# StepperMotorAuxBoard.net
KiCad netlist of a schematic drawn in Altium Designer
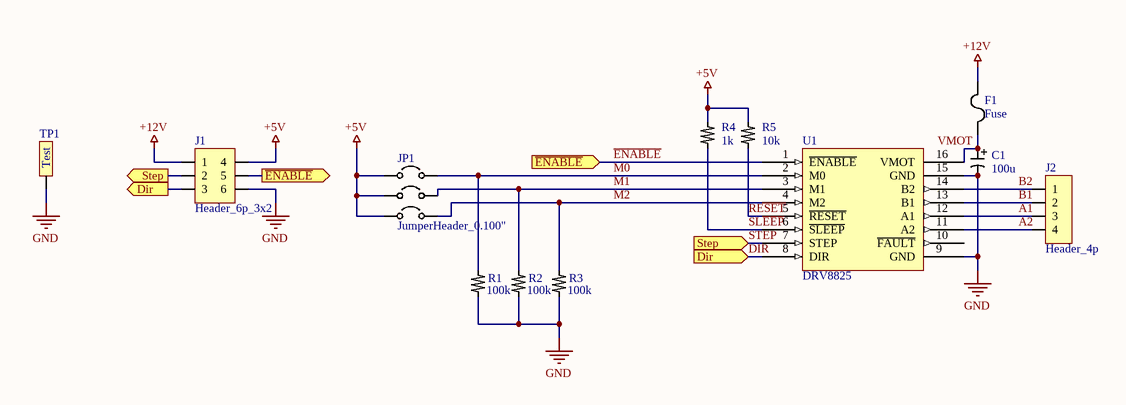
[diagram p0: StepperMotorAuxBoard.SchDoc]

(export (version "E")
  (design (tool "Eeschema 10.0.6"))
  (components
    (comp (ref "C1")
      (value "100u")
      (footprint "Capacitor_UVZ2A101MPD")
      (libsource (lib "Schlib") (part "Capacitor Polarized"))
    )
    (comp (ref "F1") (value "Fuse") (footprint "1812_PTC") (libsource (lib "MikesLib") (part "Fuse")))
    (comp (ref "J1")
      (value "Header_6p_3x2")
      (footprint "MOLEX_MiniFitJr_6p")
      (libsource (lib "MikesLib") (part "Header_6p_3x2"))
    )
    (comp (ref "J2")
      (value "Header_4p")
      (footprint "JST-XH_4p")
      (libsource (lib "Schlib") (part "Header_4p"))
    )
    (comp (ref "JP1")
      (value "JumperHeader_0.100\"")
      (footprint "JumperHeader_0.100\"")
      (libsource (lib "Schlib") (part "JumperHeader_0.100{dblquote}"))
    )
    (comp (ref "R1") (value "100k") (footprint "0805") (libsource (lib "Schlib") (part "Resistor")))
    (comp (ref "R2") (value "100k") (footprint "0805") (libsource (lib "Schlib") (part "Resistor")))
    (comp (ref "R3") (value "100k") (footprint "0805") (libsource (lib "Schlib") (part "Resistor")))
    (comp (ref "R4") (value "1k") (footprint "0805") (libsource (lib "Schlib") (part "Resistor")))
    (comp (ref "R5") (value "10k") (footprint "0805") (libsource (lib "Schlib") (part "Resistor")))
    (comp (ref "TP1")
      (value "TestPoint")
      (footprint "MikesLib:TestPoint")
      (libsource (lib "MikesLib") (part "TestPoint"))
    )
    (comp (ref "U1")
      (value "DRV8825")
      (footprint "DRV8825")
      (description "Stepper motor driver")
      (libsource (lib "Schlib") (part "DRV8825"))
    )
  )
  (nets
    (net (code "1") (name "+5V") (class "Default")
      (node (ref "J1") (pin "4") (pinfunction "4_4") (pintype "passive"))
      (node (ref "JP1") (pin "2") (pinfunction "2_2") (pintype "passive"))
      (node (ref "JP1") (pin "4") (pinfunction "4_4") (pintype "passive"))
      (node (ref "JP1") (pin "6") (pinfunction "6_6") (pintype "passive"))
      (node (ref "R4") (pin "2") (pinfunction "2_2") (pintype "passive"))
      (node (ref "R5") (pin "2") (pinfunction "2_2") (pintype "passive"))
    )
    (net (code "2") (name "+12V") (class "Default")
      (node (ref "F1") (pin "2") (pinfunction "2_2") (pintype "passive"))
      (node (ref "J1") (pin "1") (pinfunction "1_1") (pintype "passive"))
    )
    (net (code "3") (name "/A1") (class "Default")
      (node (ref "J2") (pin "3") (pinfunction "3_3") (pintype "passive"))
      (node (ref "U1") (pin "12") (pinfunction "A1_12") (pintype "output"))
    )
    (net (code "4") (name "/A2") (class "Default")
      (node (ref "J2") (pin "4") (pinfunction "4_4") (pintype "passive"))
      (node (ref "U1") (pin "11") (pinfunction "A2_11") (pintype "output"))
    )
    (net (code "5") (name "/B1") (class "Default")
      (node (ref "J2") (pin "2") (pinfunction "2_2") (pintype "passive"))
      (node (ref "U1") (pin "13") (pinfunction "B1_13") (pintype "output"))
    )
    (net (code "6") (name "/B2") (class "Default")
      (node (ref "J2") (pin "1") (pinfunction "1_1") (pintype "passive"))
      (node (ref "U1") (pin "14") (pinfunction "B2_14") (pintype "output"))
    )
    (net (code "7") (name "/DIR") (class "Default")
      (node (ref "J1") (pin "3") (pinfunction "3_3") (pintype "passive"))
      (node (ref "U1") (pin "8") (pinfunction "DIR_8") (pintype "input"))
    )
    (net (code "8") (name "/M0") (class "Default")
      (node (ref "JP1") (pin "1") (pinfunction "1_1") (pintype "passive"))
      (node (ref "R1") (pin "2") (pinfunction "2_2") (pintype "passive"))
      (node (ref "U1") (pin "2") (pinfunction "M0_2") (pintype "input"))
    )
    (net (code "9") (name "/M1") (class "Default")
      (node (ref "JP1") (pin "3") (pinfunction "3_3") (pintype "passive"))
      (node (ref "R2") (pin "2") (pinfunction "2_2") (pintype "passive"))
      (node (ref "U1") (pin "3") (pinfunction "M1_3") (pintype "input"))
    )
    (net (code "10") (name "/M2") (class "Default")
      (node (ref "JP1") (pin "5") (pinfunction "5_5") (pintype "passive"))
      (node (ref "R3") (pin "2") (pinfunction "2_2") (pintype "passive"))
      (node (ref "U1") (pin "4") (pinfunction "M2_4") (pintype "input"))
    )
    (net (code "11") (name "/STEP") (class "Default")
      (node (ref "J1") (pin "2") (pinfunction "2_2") (pintype "passive"))
      (node (ref "U1") (pin "7") (pinfunction "STEP_7") (pintype "input"))
    )
    (net (code "13") (name "/~{ENABLE}") (class "Default")
      (node (ref "J1") (pin "5") (pinfunction "5_5") (pintype "passive"))
      (node (ref "U1") (pin "1") (pinfunction "~{ENABLE}_1") (pintype "input"))
    )
    (net (code "14") (name "/~{RESET}") (class "Default")
      (node (ref "R5") (pin "1") (pinfunction "1_1") (pintype "passive"))
      (node (ref "U1") (pin "5") (pinfunction "~{RESET}_5") (pintype "input"))
    )
    (net (code "15") (name "/~{SLEEP}") (class "Default")
      (node (ref "R4") (pin "1") (pinfunction "1_1") (pintype "passive"))
      (node (ref "U1") (pin "6") (pinfunction "~{SLEEP}_6") (pintype "input"))
    )
    (net (code "16") (name "GND") (class "Default")
      (node (ref "C1") (pin "K") (pinfunction "K_K") (pintype "passive"))
      (node (ref "J1") (pin "6") (pinfunction "6_6") (pintype "passive"))
      (node (ref "R1") (pin "1") (pinfunction "1_1") (pintype "passive"))
      (node (ref "R2") (pin "1") (pinfunction "1_1") (pintype "passive"))
      (node (ref "R3") (pin "1") (pinfunction "1_1") (pintype "passive"))
      (node (ref "TP1") (pin "1") (pinfunction "1_1") (pintype "passive"))
      (node (ref "U1") (pin "15") (pinfunction "GND_15") (pintype "power_in"))
      (node (ref "U1") (pin "9") (pinfunction "GND_9") (pintype "power_in"))
    )
    (net (code "17") (name "Net-(U1-VMOT)") (class "Default")
      (node (ref "C1") (pin "A") (pinfunction "A_A") (pintype "passive"))
      (node (ref "F1") (pin "1") (pinfunction "1_1") (pintype "passive"))
      (node (ref "U1") (pin "16") (pinfunction "VMOT_16") (pintype "power_in"))
    )
    (net (code "18") (name "unconnected-(U1-~{FAULT}-Pad10)") (class "Default")
      (node (ref "U1") (pin "10") (pinfunction "~{FAULT}_10") (pintype "output"))
    )
  )
)
